# Sheet2.net
KiCad netlist of a schematic drawn in Altium Designer
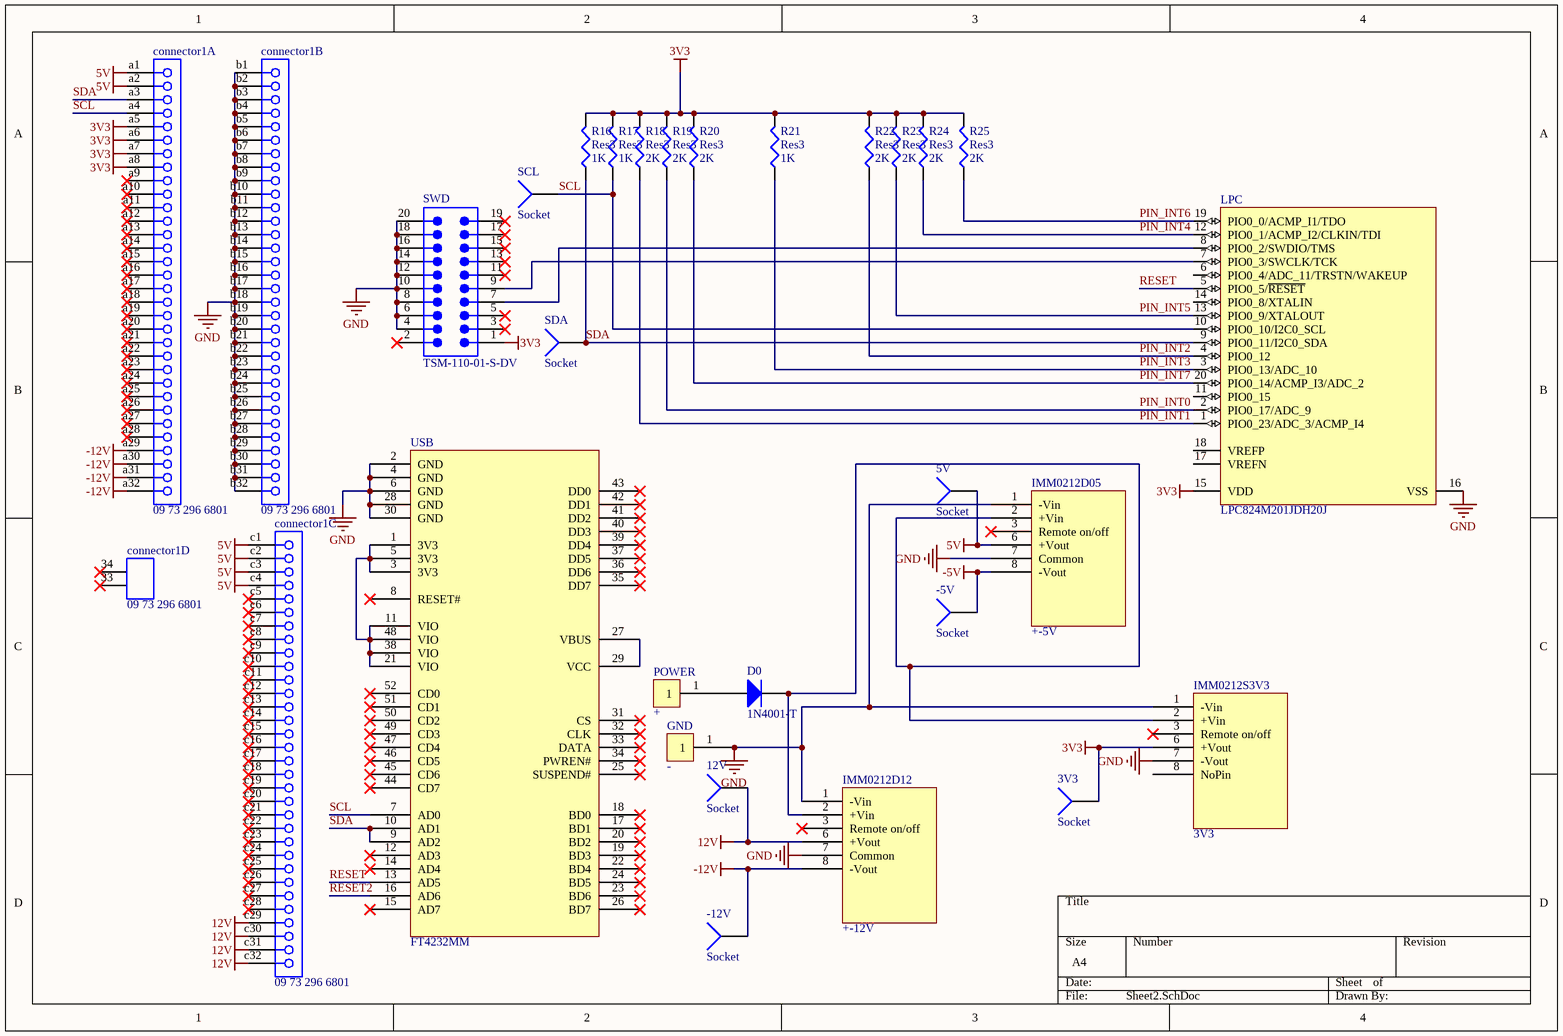
[diagram p0: Sheet2.SchDoc]

(export (version "E")
  (design (tool "Eeschema 10.0.6"))
  (components
    (comp (ref "-5V")
      (value "Socket")
      (footprint "CON1")
      (fields (field (name "PUBLISHER") "Altium Limited"))
      (libsource (lib "Miscellaneous Connectors") (part "Socket"))
    )
    (comp (ref "-12V")
      (value "Socket")
      (footprint "CON1")
      (fields (field (name "PUBLISHER") "Altium Limited"))
      (libsource (lib "Miscellaneous Connectors") (part "Socket"))
    )
    (comp (ref "3V3")
      (value "Socket")
      (footprint "CON1")
      (fields (field (name "PUBLISHER") "Altium Limited"))
      (libsource (lib "Miscellaneous Connectors") (part "Socket"))
    )
    (comp (ref "5V")
      (value "Socket")
      (footprint "CON1")
      (fields (field (name "PUBLISHER") "Altium Limited"))
      (libsource (lib "Miscellaneous Connectors") (part "Socket"))
    )
    (comp (ref "12V")
      (value "Socket")
      (footprint "CON1")
      (fields (field (name "PUBLISHER") "Altium Limited"))
      (libsource (lib "Miscellaneous Connectors") (part "Socket"))
    )
    (comp (ref "connector1")
      (value "09 73 296 6801")
      (footprint "DAC testerPCB:0973296X801")
      (fields (field (name "PUBLISHER") "Altium Limited"))
      (libsource (lib "HARTING DIN 41612 Type R") (part "09 73 296 6801"))
    )
    (comp (ref "D0")
      (value "1N4001-T")
      (footprint "DIOD-DO-41-P-2_V")
      (description "1.0 A Rectifier, 15 pF, 50 V, -65 to 150 degC, 2-Pin DO-41 Plastic, RoHS, Tape and Reel")
      (fields (field (name "MANUFACTURER") "Diodes Inc"))
      (libsource (lib "Altium Content Vault") (part "CMP-0639-00006-2"))
    )
    (comp (ref "GND") (value "-") (footprint "RA") (libsource (lib "schlib") (part "Power")))
    (comp (ref "IMM0212D05")
      (value "+-5V")
      (footprint "my_pcb:SIP8")
      (libsource (lib "schlib") (part "IMM0212D05"))
    )
    (comp (ref "IMM0212D12")
      (value "+-12V")
      (footprint "SIP8")
      (libsource (lib "schlib") (part "IMM0212D05"))
    )
    (comp (ref "IMM0212S3V3")
      (value "3V3")
      (footprint "my_pcb:SIP8")
      (libsource (lib "schlib") (part "Component_1"))
    )
    (comp (ref "LPC")
      (value "LPC824M201JDH20J")
      (footprint "NXP-SOT360-1_N")
      (fields
        (field (name "MANUFACTURER") "NXP Semiconductors")
        (field (name "PARTNUMBER") "LPC824M201JDH20")
      )
      (libsource (lib "Altium Content Vault") (part "CMP-0173-00095-1"))
    )
    (comp (ref "POWER") (value "+") (footprint "RA") (libsource (lib "schlib") (part "Power")))
    (comp (ref "R16")
      (value "Res3")
      (footprint "J1-0603")
      (description "Resistor")
      (fields (field (name "ALTIUM_VALUE") "1K") (field (name "PUBLISHER") "Altium Limited"))
      (libsource (lib "Miscellaneous Devices") (part "Res3"))
    )
    (comp (ref "R17")
      (value "Res3")
      (footprint "J1-0603")
      (description "Resistor")
      (fields (field (name "ALTIUM_VALUE") "1K") (field (name "PUBLISHER") "Altium Limited"))
      (libsource (lib "Miscellaneous Devices") (part "Res3"))
    )
    (comp (ref "R18")
      (value "Res3")
      (footprint "J1-0603")
      (description "Resistor")
      (fields (field (name "ALTIUM_VALUE") "2K") (field (name "PUBLISHER") "Altium Limited"))
      (libsource (lib "Miscellaneous Devices") (part "Res3"))
    )
    (comp (ref "R19")
      (value "Res3")
      (footprint "J1-0603")
      (description "Resistor")
      (fields (field (name "ALTIUM_VALUE") "2K") (field (name "PUBLISHER") "Altium Limited"))
      (libsource (lib "Miscellaneous Devices") (part "Res3"))
    )
    (comp (ref "R20")
      (value "Res3")
      (footprint "J1-0603")
      (description "Resistor")
      (fields (field (name "ALTIUM_VALUE") "2K") (field (name "PUBLISHER") "Altium Limited"))
      (libsource (lib "Miscellaneous Devices") (part "Res3"))
    )
    (comp (ref "R21")
      (value "Res3")
      (footprint "J1-0603")
      (description "Resistor")
      (fields (field (name "ALTIUM_VALUE") "1K") (field (name "PUBLISHER") "Altium Limited"))
      (libsource (lib "Miscellaneous Devices") (part "Res3"))
    )
    (comp (ref "R22")
      (value "Res3")
      (footprint "J1-0603")
      (description "Resistor")
      (fields (field (name "ALTIUM_VALUE") "2K") (field (name "PUBLISHER") "Altium Limited"))
      (libsource (lib "Miscellaneous Devices") (part "Res3"))
    )
    (comp (ref "R23")
      (value "Res3")
      (footprint "J1-0603")
      (description "Resistor")
      (fields (field (name "ALTIUM_VALUE") "2K") (field (name "PUBLISHER") "Altium Limited"))
      (libsource (lib "Miscellaneous Devices") (part "Res3"))
    )
    (comp (ref "R24")
      (value "Res3")
      (footprint "J1-0603")
      (description "Resistor")
      (fields (field (name "ALTIUM_VALUE") "2K") (field (name "PUBLISHER") "Altium Limited"))
      (libsource (lib "Miscellaneous Devices") (part "Res3"))
    )
    (comp (ref "R25")
      (value "Res3")
      (footprint "J1-0603")
      (description "Resistor")
      (fields (field (name "ALTIUM_VALUE") "2K") (field (name "PUBLISHER") "Altium Limited"))
      (libsource (lib "Miscellaneous Devices") (part "Res3"))
    )
    (comp (ref "SCL")
      (value "Socket")
      (footprint "CON1")
      (fields (field (name "PUBLISHER") "Altium Limited"))
      (libsource (lib "Miscellaneous Connectors") (part "Socket"))
    )
    (comp (ref "SDA")
      (value "Socket")
      (footprint "CON1")
      (fields (field (name "PUBLISHER") "Altium Limited"))
      (libsource (lib "Miscellaneous Connectors") (part "Socket"))
    )
    (comp (ref "SWD")
      (value "TSM-110-01-S-DV")
      (footprint "SMTC-TSM-110-01-X-DV")
      (fields (field (name "MANUFACTURER") "Samtec"))
      (libsource (lib "Altium Content Vault") (part "CMP-1024-00283-1"))
    )
    (comp (ref "USB")
      (value "FT4232MM")
      (footprint "ICfootprint3:FT4232MM")
      (description "FDTI mini module")
      (libsource (lib "nxp_device") (part "FT4232MM"))
    )
  )
  (nets
    (net (code "1") (name "-5V") (class "Default")
      (node (ref "-5V") (pin "1") (pinfunction "1_1") (pintype "passive"))
      (node (ref "IMM0212D05") (pin "8") (pinfunction "-Vout_8") (pintype "passive"))
    )
    (net (code "2") (name "-12V") (class "Default")
      (node (ref "-12V") (pin "1") (pinfunction "1_1") (pintype "passive"))
      (node (ref "IMM0212D12") (pin "8") (pinfunction "-Vout_8") (pintype "passive"))
      (node (ref "connector1") (pin "a29") (pinfunction "a29_a29") (pintype "passive"))
      (node (ref "connector1") (pin "a30") (pinfunction "a30_a30") (pintype "passive"))
      (node (ref "connector1") (pin "a31") (pinfunction "a31_a31") (pintype "passive"))
      (node (ref "connector1") (pin "a32") (pinfunction "a32_a32") (pintype "passive"))
    )
    (net (code "3") (name "/PIN_INT0") (class "Default")
      (node (ref "LPC") (pin "2") (pinfunction "PIO0_17/ADC_9_2") (pintype "bidirectional"))
      (node (ref "R19") (pin "1") (pinfunction "1_1") (pintype "passive"))
    )
    (net (code "4") (name "/PIN_INT1") (class "Default")
      (node (ref "LPC") (pin "1") (pinfunction "PIO0_23/ADC_3/ACMP_I4_1") (pintype "bidirectional"))
      (node (ref "R18") (pin "1") (pinfunction "1_1") (pintype "passive"))
    )
    (net (code "5") (name "/PIN_INT2") (class "Default")
      (node (ref "LPC") (pin "4") (pinfunction "PIO0_12_4") (pintype "bidirectional"))
      (node (ref "R22") (pin "1") (pinfunction "1_1") (pintype "passive"))
    )
    (net (code "6") (name "/PIN_INT3") (class "Default")
      (node (ref "LPC") (pin "3") (pinfunction "PIO0_13/ADC_10_3") (pintype "bidirectional"))
      (node (ref "R21") (pin "1") (pinfunction "1_1") (pintype "passive"))
    )
    (net (code "7") (name "/PIN_INT4") (class "Default")
      (node (ref "LPC") (pin "12") (pinfunction "PIO0_1/ACMP_I2/CLKIN/TDI_12") (pintype "bidirectional"))
      (node (ref "R24") (pin "1") (pinfunction "1_1") (pintype "passive"))
    )
    (net (code "8") (name "/PIN_INT5") (class "Default")
      (node (ref "LPC") (pin "13") (pinfunction "PIO0_9/XTALOUT_13") (pintype "bidirectional"))
      (node (ref "R23") (pin "1") (pinfunction "1_1") (pintype "passive"))
    )
    (net (code "9") (name "/PIN_INT6") (class "Default")
      (node (ref "LPC") (pin "19") (pinfunction "PIO0_0/ACMP_I1/TDO_19") (pintype "bidirectional"))
      (node (ref "R25") (pin "1") (pinfunction "1_1") (pintype "passive"))
    )
    (net (code "10") (name "/PIN_INT7") (class "Default")
      (node (ref "LPC") (pin "20") (pinfunction "PIO0_14/ACMP_I3/ADC_2_20") (pintype "bidirectional"))
      (node (ref "R20") (pin "1") (pinfunction "1_1") (pintype "passive"))
    )
    (net (code "11") (name "/RESET") (class "Default")
      (node (ref "LPC") (pin "5") (pinfunction "PIO0_5/~{RESET}_5") (pintype "bidirectional"))
      (node (ref "USB") (pin "13") (pinfunction "AD5_13") (pintype "passive"))
    )
    (net (code "12") (name "/RESET2") (class "Default")
      (node (ref "USB") (pin "16") (pinfunction "AD6_16") (pintype "passive"))
    )
    (net (code "13") (name "/SCL") (class "Default")
      (node (ref "LPC") (pin "10") (pinfunction "PIO0_10/I2C0_SCL_10") (pintype "bidirectional"))
      (node (ref "R17") (pin "1") (pinfunction "1_1") (pintype "passive"))
      (node (ref "SCL") (pin "1") (pinfunction "1_1") (pintype "passive"))
      (node (ref "USB") (pin "7") (pinfunction "AD0_7") (pintype "passive"))
      (node (ref "connector1") (pin "a4") (pinfunction "a4_a4") (pintype "passive"))
    )
    (net (code "14") (name "/SDA") (class "Default")
      (node (ref "LPC") (pin "9") (pinfunction "PIO0_11/I2C0_SDA_9") (pintype "bidirectional"))
      (node (ref "R16") (pin "1") (pinfunction "1_1") (pintype "passive"))
      (node (ref "SDA") (pin "1") (pinfunction "1_1") (pintype "passive"))
      (node (ref "USB") (pin "10") (pinfunction "AD1_10") (pintype "passive"))
      (node (ref "USB") (pin "9") (pinfunction "AD2_9") (pintype "passive"))
      (node (ref "connector1") (pin "a3") (pinfunction "a3_a3") (pintype "passive"))
    )
    (net (code "15") (name "3V3") (class "Default")
      (node (ref "3V3") (pin "1") (pinfunction "1_1") (pintype "passive"))
      (node (ref "IMM0212S3V3") (pin "6") (pinfunction "+Vout_6") (pintype "passive"))
      (node (ref "LPC") (pin "15") (pinfunction "VDD_15") (pintype "power_in"))
      (node (ref "R16") (pin "2") (pinfunction "2_2") (pintype "passive"))
      (node (ref "R17") (pin "2") (pinfunction "2_2") (pintype "passive"))
      (node (ref "R18") (pin "2") (pinfunction "2_2") (pintype "passive"))
      (node (ref "R19") (pin "2") (pinfunction "2_2") (pintype "passive"))
      (node (ref "R20") (pin "2") (pinfunction "2_2") (pintype "passive"))
      (node (ref "R21") (pin "2") (pinfunction "2_2") (pintype "passive"))
      (node (ref "R22") (pin "2") (pinfunction "2_2") (pintype "passive"))
      (node (ref "R23") (pin "2") (pinfunction "2_2") (pintype "passive"))
      (node (ref "R24") (pin "2") (pinfunction "2_2") (pintype "passive"))
      (node (ref "R25") (pin "2") (pinfunction "2_2") (pintype "passive"))
      (node (ref "SWD") (pin "1") (pinfunction "1_1") (pintype "passive"))
      (node (ref "connector1") (pin "a5") (pinfunction "a5_a5") (pintype "passive"))
      (node (ref "connector1") (pin "a6") (pinfunction "a6_a6") (pintype "passive"))
      (node (ref "connector1") (pin "a7") (pinfunction "a7_a7") (pintype "passive"))
      (node (ref "connector1") (pin "a8") (pinfunction "a8_a8") (pintype "passive"))
    )
    (net (code "16") (name "5V") (class "Default")
      (node (ref "5V") (pin "1") (pinfunction "1_1") (pintype "passive"))
      (node (ref "IMM0212D05") (pin "6") (pinfunction "+Vout_6") (pintype "passive"))
      (node (ref "connector1") (pin "a1") (pinfunction "a1_a1") (pintype "passive"))
      (node (ref "connector1") (pin "a2") (pinfunction "a2_a2") (pintype "passive"))
      (node (ref "connector1") (pin "c1") (pinfunction "c1_c1") (pintype "passive"))
      (node (ref "connector1") (pin "c2") (pinfunction "c2_c2") (pintype "passive"))
      (node (ref "connector1") (pin "c3") (pinfunction "c3_c3") (pintype "passive"))
      (node (ref "connector1") (pin "c4") (pinfunction "c4_c4") (pintype "passive"))
    )
    (net (code "17") (name "12V") (class "Default")
      (node (ref "12V") (pin "1") (pinfunction "1_1") (pintype "passive"))
      (node (ref "IMM0212D12") (pin "6") (pinfunction "+Vout_6") (pintype "passive"))
      (node (ref "connector1") (pin "c29") (pinfunction "c29_c29") (pintype "passive"))
      (node (ref "connector1") (pin "c30") (pinfunction "c30_c30") (pintype "passive"))
      (node (ref "connector1") (pin "c31") (pinfunction "c31_c31") (pintype "passive"))
      (node (ref "connector1") (pin "c32") (pinfunction "c32_c32") (pintype "passive"))
    )
    (net (code "18") (name "GND") (class "Default")
      (node (ref "GND") (pin "1") (pinfunction "1_1") (pintype "passive"))
      (node (ref "IMM0212D05") (pin "1") (pinfunction "-Vin_1") (pintype "passive"))
      (node (ref "IMM0212D05") (pin "7") (pinfunction "Common_7") (pintype "passive"))
      (node (ref "IMM0212D12") (pin "1") (pinfunction "-Vin_1") (pintype "passive"))
      (node (ref "IMM0212D12") (pin "7") (pinfunction "Common_7") (pintype "passive"))
      (node (ref "IMM0212S3V3") (pin "1") (pinfunction "-Vin_1") (pintype "passive"))
      (node (ref "IMM0212S3V3") (pin "7") (pinfunction "-Vout_7") (pintype "passive"))
      (node (ref "LPC") (pin "16") (pinfunction "VSS_16") (pintype "power_in"))
      (node (ref "SWD") (pin "10") (pinfunction "10_10") (pintype "passive"))
      (node (ref "SWD") (pin "12") (pinfunction "12_12") (pintype "passive"))
      (node (ref "SWD") (pin "14") (pinfunction "14_14") (pintype "passive"))
      (node (ref "SWD") (pin "16") (pinfunction "16_16") (pintype "passive"))
      (node (ref "SWD") (pin "18") (pinfunction "18_18") (pintype "passive"))
      (node (ref "SWD") (pin "20") (pinfunction "20_20") (pintype "passive"))
      (node (ref "SWD") (pin "4") (pinfunction "4_4") (pintype "passive"))
      (node (ref "SWD") (pin "6") (pinfunction "6_6") (pintype "passive"))
      (node (ref "SWD") (pin "8") (pinfunction "8_8") (pintype "passive"))
      (node (ref "USB") (pin "2") (pinfunction "GND_2") (pintype "passive"))
      (node (ref "USB") (pin "28") (pinfunction "GND_28") (pintype "passive"))
      (node (ref "USB") (pin "30") (pinfunction "GND_30") (pintype "passive"))
      (node (ref "USB") (pin "4") (pinfunction "GND_4") (pintype "passive"))
      (node (ref "USB") (pin "6") (pinfunction "GND_6") (pintype "passive"))
      (node (ref "connector1") (pin "b1") (pinfunction "b1_b1") (pintype "passive"))
      (node (ref "connector1") (pin "b10") (pinfunction "b10_b10") (pintype "passive"))
      (node (ref "connector1") (pin "b11") (pinfunction "b11_b11") (pintype "passive"))
      (node (ref "connector1") (pin "b12") (pinfunction "b12_b12") (pintype "passive"))
      (node (ref "connector1") (pin "b13") (pinfunction "b13_b13") (pintype "passive"))
      (node (ref "connector1") (pin "b14") (pinfunction "b14_b14") (pintype "passive"))
      (node (ref "connector1") (pin "b15") (pinfunction "b15_b15") (pintype "passive"))
      (node (ref "connector1") (pin "b16") (pinfunction "b16_b16") (pintype "passive"))
      (node (ref "connector1") (pin "b17") (pinfunction "b17_b17") (pintype "passive"))
      (node (ref "connector1") (pin "b18") (pinfunction "b18_b18") (pintype "passive"))
      (node (ref "connector1") (pin "b19") (pinfunction "b19_b19") (pintype "passive"))
      (node (ref "connector1") (pin "b2") (pinfunction "b2_b2") (pintype "passive"))
      (node (ref "connector1") (pin "b20") (pinfunction "b20_b20") (pintype "passive"))
      (node (ref "connector1") (pin "b21") (pinfunction "b21_b21") (pintype "passive"))
      (node (ref "connector1") (pin "b22") (pinfunction "b22_b22") (pintype "passive"))
      (node (ref "connector1") (pin "b23") (pinfunction "b23_b23") (pintype "passive"))
      (node (ref "connector1") (pin "b24") (pinfunction "b24_b24") (pintype "passive"))
      (node (ref "connector1") (pin "b25") (pinfunction "b25_b25") (pintype "passive"))
      (node (ref "connector1") (pin "b26") (pinfunction "b26_b26") (pintype "passive"))
      (node (ref "connector1") (pin "b27") (pinfunction "b27_b27") (pintype "passive"))
      (node (ref "connector1") (pin "b28") (pinfunction "b28_b28") (pintype "passive"))
      (node (ref "connector1") (pin "b29") (pinfunction "b29_b29") (pintype "passive"))
      (node (ref "connector1") (pin "b3") (pinfunction "b3_b3") (pintype "passive"))
      (node (ref "connector1") (pin "b30") (pinfunction "b30_b30") (pintype "passive"))
      (node (ref "connector1") (pin "b31") (pinfunction "b31_b31") (pintype "passive"))
      (node (ref "connector1") (pin "b32") (pinfunction "b32_b32") (pintype "passive"))
      (node (ref "connector1") (pin "b4") (pinfunction "b4_b4") (pintype "passive"))
      (node (ref "connector1") (pin "b5") (pinfunction "b5_b5") (pintype "passive"))
      (node (ref "connector1") (pin "b6") (pinfunction "b6_b6") (pintype "passive"))
      (node (ref "connector1") (pin "b7") (pinfunction "b7_b7") (pintype "passive"))
      (node (ref "connector1") (pin "b8") (pinfunction "b8_b8") (pintype "passive"))
      (node (ref "connector1") (pin "b9") (pinfunction "b9_b9") (pintype "passive"))
    )
    (net (code "19") (name "Net-(D0-A)") (class "Default")
      (node (ref "D0") (pin "1") (pinfunction "A_1") (pintype "passive"))
      (node (ref "POWER") (pin "1") (pinfunction "1_1") (pintype "passive"))
    )
    (net (code "20") (name "Net-(D0-K)") (class "Default")
      (node (ref "D0") (pin "2") (pinfunction "K_2") (pintype "passive"))
      (node (ref "IMM0212D05") (pin "2") (pinfunction "+Vin_2") (pintype "passive"))
      (node (ref "IMM0212D12") (pin "2") (pinfunction "+Vin_2") (pintype "passive"))
      (node (ref "IMM0212S3V3") (pin "2") (pinfunction "+Vin_2") (pintype "passive"))
    )
    (net (code "21") (name "Net-(LPC-PIO0_2{slash}SWDIO{slash}TMS)") (class "Default")
      (node (ref "LPC") (pin "8") (pinfunction "PIO0_2/SWDIO/TMS_8") (pintype "bidirectional"))
      (node (ref "SWD") (pin "7") (pinfunction "7_7") (pintype "passive"))
    )
    (net (code "22") (name "Net-(LPC-PIO0_3{slash}SWCLK{slash}TCK)") (class "Default")
      (node (ref "LPC") (pin "7") (pinfunction "PIO0_3/SWCLK/TCK_7") (pintype "bidirectional"))
      (node (ref "SWD") (pin "9") (pinfunction "9_9") (pintype "passive"))
    )
    (net (code "23") (name "Net-(USB-3V3-Pad1)") (class "Default")
      (node (ref "USB") (pin "1") (pinfunction "3V3_1") (pintype "passive"))
      (node (ref "USB") (pin "11") (pinfunction "VIO_11") (pintype "passive"))
      (node (ref "USB") (pin "21") (pinfunction "VIO_21") (pintype "passive"))
      (node (ref "USB") (pin "3") (pinfunction "3V3_3") (pintype "passive"))
      (node (ref "USB") (pin "38") (pinfunction "VIO_38") (pintype "passive"))
      (node (ref "USB") (pin "48") (pinfunction "VIO_48") (pintype "passive"))
      (node (ref "USB") (pin "5") (pinfunction "3V3_5") (pintype "passive"))
    )
    (net (code "24") (name "Net-(USB-VBUS)") (class "Default")
      (node (ref "USB") (pin "27") (pinfunction "VBUS_27") (pintype "passive"))
      (node (ref "USB") (pin "29") (pinfunction "VCC_29") (pintype "passive"))
    )
    (net (code "25") (name "unconnected-(IMM0212D05-Remote_on{slash}off-Pad3)") (class "Default")
      (node (ref "IMM0212D05") (pin "3") (pinfunction "Remote_on/off_3") (pintype "passive+no_connect"))
    )
    (net (code "26") (name "unconnected-(IMM0212D12-Remote_on{slash}off-Pad3)") (class "Default")
      (node (ref "IMM0212D12") (pin "3") (pinfunction "Remote_on/off_3") (pintype "passive+no_connect"))
    )
    (net (code "27") (name "unconnected-(IMM0212S3V3-NoPin-Pad8)") (class "Default")
      (node (ref "IMM0212S3V3") (pin "8") (pinfunction "NoPin_8") (pintype "passive"))
    )
    (net (code "28") (name "unconnected-(IMM0212S3V3-Remote_on{slash}off-Pad3)") (class "Default")
      (node (ref "IMM0212S3V3") (pin "3") (pinfunction "Remote_on/off_3") (pintype "passive+no_connect"))
    )
    (net (code "29") (name "unconnected-(LPC-PIO0_4{slash}ADC_11{slash}TRSTN{slash}WAKEUP-Pad6)") (class "Default")
      (node (ref "LPC") (pin "6") (pinfunction "PIO0_4/ADC_11/TRSTN/WAKEUP_6") (pintype "bidirectional"))
    )
    (net (code "30") (name "unconnected-(LPC-PIO0_8{slash}XTALIN-Pad14)") (class "Default")
      (node (ref "LPC") (pin "14") (pinfunction "PIO0_8/XTALIN_14") (pintype "bidirectional"))
    )
    (net (code "31") (name "unconnected-(LPC-PIO0_15-Pad11)") (class "Default")
      (node (ref "LPC") (pin "11") (pinfunction "PIO0_15_11") (pintype "bidirectional"))
    )
    (net (code "32") (name "unconnected-(LPC-VREFN-Pad17)") (class "Default")
      (node (ref "LPC") (pin "17") (pinfunction "VREFN_17") (pintype "power_in"))
    )
    (net (code "33") (name "unconnected-(LPC-VREFP-Pad18)") (class "Default")
      (node (ref "LPC") (pin "18") (pinfunction "VREFP_18") (pintype "power_in"))
    )
    (net (code "34") (name "unconnected-(SWD-Pad2)") (class "Default")
      (node (ref "SWD") (pin "2") (pinfunction "2_2") (pintype "passive+no_connect"))
    )
    (net (code "35") (name "unconnected-(SWD-Pad3)") (class "Default")
      (node (ref "SWD") (pin "3") (pinfunction "3_3") (pintype "passive+no_connect"))
    )
    (net (code "36") (name "unconnected-(SWD-Pad5)") (class "Default")
      (node (ref "SWD") (pin "5") (pinfunction "5_5") (pintype "passive+no_connect"))
    )
    (net (code "37") (name "unconnected-(SWD-Pad11)") (class "Default")
      (node (ref "SWD") (pin "11") (pinfunction "11_11") (pintype "passive+no_connect"))
    )
    (net (code "38") (name "unconnected-(SWD-Pad13)") (class "Default")
      (node (ref "SWD") (pin "13") (pinfunction "13_13") (pintype "passive+no_connect"))
    )
    (net (code "39") (name "unconnected-(SWD-Pad15)") (class "Default")
      (node (ref "SWD") (pin "15") (pinfunction "15_15") (pintype "passive+no_connect"))
    )
    (net (code "40") (name "unconnected-(SWD-Pad17)") (class "Default")
      (node (ref "SWD") (pin "17") (pinfunction "17_17") (pintype "passive+no_connect"))
    )
    (net (code "41") (name "unconnected-(SWD-Pad19)") (class "Default")
      (node (ref "SWD") (pin "19") (pinfunction "19_19") (pintype "passive+no_connect"))
    )
    (net (code "42") (name "unconnected-(USB-AD3-Pad12)") (class "Default")
      (node (ref "USB") (pin "12") (pinfunction "AD3_12") (pintype "passive+no_connect"))
    )
    (net (code "43") (name "unconnected-(USB-AD4-Pad14)") (class "Default")
      (node (ref "USB") (pin "14") (pinfunction "AD4_14") (pintype "passive+no_connect"))
    )
    (net (code "44") (name "unconnected-(USB-AD7-Pad15)") (class "Default")
      (node (ref "USB") (pin "15") (pinfunction "AD7_15") (pintype "passive+no_connect"))
    )
    (net (code "45") (name "unconnected-(USB-BD0-Pad18)") (class "Default")
      (node (ref "USB") (pin "18") (pinfunction "BD0_18") (pintype "passive+no_connect"))
    )
    (net (code "46") (name "unconnected-(USB-BD1-Pad17)") (class "Default")
      (node (ref "USB") (pin "17") (pinfunction "BD1_17") (pintype "passive+no_connect"))
    )
    (net (code "47") (name "unconnected-(USB-BD2-Pad20)") (class "Default")
      (node (ref "USB") (pin "20") (pinfunction "BD2_20") (pintype "passive+no_connect"))
    )
    (net (code "48") (name "unconnected-(USB-BD3-Pad19)") (class "Default")
      (node (ref "USB") (pin "19") (pinfunction "BD3_19") (pintype "passive+no_connect"))
    )
    (net (code "49") (name "unconnected-(USB-BD4-Pad22)") (class "Default")
      (node (ref "USB") (pin "22") (pinfunction "BD4_22") (pintype "passive+no_connect"))
    )
    (net (code "50") (name "unconnected-(USB-BD5-Pad24)") (class "Default")
      (node (ref "USB") (pin "24") (pinfunction "BD5_24") (pintype "passive+no_connect"))
    )
    (net (code "51") (name "unconnected-(USB-BD6-Pad23)") (class "Default")
      (node (ref "USB") (pin "23") (pinfunction "BD6_23") (pintype "passive+no_connect"))
    )
    (net (code "52") (name "unconnected-(USB-BD7-Pad26)") (class "Default")
      (node (ref "USB") (pin "26") (pinfunction "BD7_26") (pintype "passive+no_connect"))
    )
    (net (code "53") (name "unconnected-(USB-CD0-Pad52)") (class "Default")
      (node (ref "USB") (pin "52") (pinfunction "CD0_52") (pintype "passive+no_connect"))
    )
    (net (code "54") (name "unconnected-(USB-CD1-Pad51)") (class "Default")
      (node (ref "USB") (pin "51") (pinfunction "CD1_51") (pintype "passive+no_connect"))
    )
    (net (code "55") (name "unconnected-(USB-CD2-Pad50)") (class "Default")
      (node (ref "USB") (pin "50") (pinfunction "CD2_50") (pintype "passive+no_connect"))
    )
    (net (code "56") (name "unconnected-(USB-CD3-Pad49)") (class "Default")
      (node (ref "USB") (pin "49") (pinfunction "CD3_49") (pintype "passive+no_connect"))
    )
    (net (code "57") (name "unconnected-(USB-CD4-Pad47)") (class "Default")
      (node (ref "USB") (pin "47") (pinfunction "CD4_47") (pintype "passive+no_connect"))
    )
    (net (code "58") (name "unconnected-(USB-CD5-Pad46)") (class "Default")
      (node (ref "USB") (pin "46") (pinfunction "CD5_46") (pintype "passive+no_connect"))
    )
    (net (code "59") (name "unconnected-(USB-CD6-Pad45)") (class "Default")
      (node (ref "USB") (pin "45") (pinfunction "CD6_45") (pintype "passive+no_connect"))
    )
    (net (code "60") (name "unconnected-(USB-CD7-Pad44)") (class "Default")
      (node (ref "USB") (pin "44") (pinfunction "CD7_44") (pintype "passive+no_connect"))
    )
    (net (code "61") (name "unconnected-(USB-CLK-Pad32)") (class "Default")
      (node (ref "USB") (pin "32") (pinfunction "CLK_32") (pintype "passive+no_connect"))
    )
    (net (code "62") (name "unconnected-(USB-CS-Pad31)") (class "Default")
      (node (ref "USB") (pin "31") (pinfunction "CS_31") (pintype "passive+no_connect"))
    )
    (net (code "63") (name "unconnected-(USB-DATA-Pad33)") (class "Default")
      (node (ref "USB") (pin "33") (pinfunction "DATA_33") (pintype "passive+no_connect"))
    )
    (net (code "64") (name "unconnected-(USB-DD0-Pad43)") (class "Default")
      (node (ref "USB") (pin "43") (pinfunction "DD0_43") (pintype "passive+no_connect"))
    )
    (net (code "65") (name "unconnected-(USB-DD1-Pad42)") (class "Default")
      (node (ref "USB") (pin "42") (pinfunction "DD1_42") (pintype "passive+no_connect"))
    )
    (net (code "66") (name "unconnected-(USB-DD2-Pad41)") (class "Default")
      (node (ref "USB") (pin "41") (pinfunction "DD2_41") (pintype "passive+no_connect"))
    )
    (net (code "67") (name "unconnected-(USB-DD3-Pad40)") (class "Default")
      (node (ref "USB") (pin "40") (pinfunction "DD3_40") (pintype "passive+no_connect"))
    )
    (net (code "68") (name "unconnected-(USB-DD4-Pad39)") (class "Default")
      (node (ref "USB") (pin "39") (pinfunction "DD4_39") (pintype "passive+no_connect"))
    )
    (net (code "69") (name "unconnected-(USB-DD5-Pad37)") (class "Default")
      (node (ref "USB") (pin "37") (pinfunction "DD5_37") (pintype "passive+no_connect"))
    )
    (net (code "70") (name "unconnected-(USB-DD6-Pad36)") (class "Default")
      (node (ref "USB") (pin "36") (pinfunction "DD6_36") (pintype "passive+no_connect"))
    )
    (net (code "71") (name "unconnected-(USB-DD7-Pad35)") (class "Default")
      (node (ref "USB") (pin "35") (pinfunction "DD7_35") (pintype "passive+no_connect"))
    )
    (net (code "72") (name "unconnected-(USB-PWREN#-Pad34)") (class "Default")
      (node (ref "USB") (pin "34") (pinfunction "PWREN#_34") (pintype "passive+no_connect"))
    )
    (net (code "73") (name "unconnected-(USB-RESET#-Pad8)") (class "Default")
      (node (ref "USB") (pin "8") (pinfunction "RESET#_8") (pintype "passive+no_connect"))
    )
    (net (code "74") (name "unconnected-(USB-SUSPEND#-Pad25)") (class "Default")
      (node (ref "USB") (pin "25") (pinfunction "SUSPEND#_25") (pintype "passive+no_connect"))
    )
    (net (code "75") (name "unconnected-(connector1-Pada9)") (class "Default")
      (node (ref "connector1") (pin "a9") (pinfunction "a9_a9") (pintype "passive+no_connect"))
    )
    (net (code "76") (name "unconnected-(connector1-Pada10)") (class "Default")
      (node (ref "connector1") (pin "a10") (pinfunction "a10_a10") (pintype "passive+no_connect"))
    )
    (net (code "77") (name "unconnected-(connector1-Pada11)") (class "Default")
      (node (ref "connector1") (pin "a11") (pinfunction "a11_a11") (pintype "passive+no_connect"))
    )
    (net (code "78") (name "unconnected-(connector1-Pada12)") (class "Default")
      (node (ref "connector1") (pin "a12") (pinfunction "a12_a12") (pintype "passive+no_connect"))
    )
    (net (code "79") (name "unconnected-(connector1-Pada13)") (class "Default")
      (node (ref "connector1") (pin "a13") (pinfunction "a13_a13") (pintype "passive+no_connect"))
    )
    (net (code "80") (name "unconnected-(connector1-Pada14)") (class "Default")
      (node (ref "connector1") (pin "a14") (pinfunction "a14_a14") (pintype "passive+no_connect"))
    )
    (net (code "81") (name "unconnected-(connector1-Pada15)") (class "Default")
      (node (ref "connector1") (pin "a15") (pinfunction "a15_a15") (pintype "passive+no_connect"))
    )
    (net (code "82") (name "unconnected-(connector1-Pada16)") (class "Default")
      (node (ref "connector1") (pin "a16") (pinfunction "a16_a16") (pintype "passive+no_connect"))
    )
    (net (code "83") (name "unconnected-(connector1-Pada17)") (class "Default")
      (node (ref "connector1") (pin "a17") (pinfunction "a17_a17") (pintype "passive+no_connect"))
    )
    (net (code "84") (name "unconnected-(connector1-Pada18)") (class "Default")
      (node (ref "connector1") (pin "a18") (pinfunction "a18_a18") (pintype "passive+no_connect"))
    )
    (net (code "85") (name "unconnected-(connector1-Pada19)") (class "Default")
      (node (ref "connector1") (pin "a19") (pinfunction "a19_a19") (pintype "passive+no_connect"))
    )
    (net (code "86") (name "unconnected-(connector1-Pada20)") (class "Default")
      (node (ref "connector1") (pin "a20") (pinfunction "a20_a20") (pintype "passive+no_connect"))
    )
    (net (code "87") (name "unconnected-(connector1-Pada21)") (class "Default")
      (node (ref "connector1") (pin "a21") (pinfunction "a21_a21") (pintype "passive+no_connect"))
    )
    (net (code "88") (name "unconnected-(connector1-Pada22)") (class "Default")
      (node (ref "connector1") (pin "a22") (pinfunction "a22_a22") (pintype "passive+no_connect"))
    )
    (net (code "89") (name "unconnected-(connector1-Pada23)") (class "Default")
      (node (ref "connector1") (pin "a23") (pinfunction "a23_a23") (pintype "passive+no_connect"))
    )
    (net (code "90") (name "unconnected-(connector1-Pada24)") (class "Default")
      (node (ref "connector1") (pin "a24") (pinfunction "a24_a24") (pintype "passive+no_connect"))
    )
    (net (code "91") (name "unconnected-(connector1-Pada25)") (class "Default")
      (node (ref "connector1") (pin "a25") (pinfunction "a25_a25") (pintype "passive+no_connect"))
    )
    (net (code "92") (name "unconnected-(connector1-Pada26)") (class "Default")
      (node (ref "connector1") (pin "a26") (pinfunction "a26_a26") (pintype "passive+no_connect"))
    )
    (net (code "93") (name "unconnected-(connector1-Pada27)") (class "Default")
      (node (ref "connector1") (pin "a27") (pinfunction "a27_a27") (pintype "passive+no_connect"))
    )
    (net (code "94") (name "unconnected-(connector1-Pada28)") (class "Default")
      (node (ref "connector1") (pin "a28") (pinfunction "a28_a28") (pintype "passive+no_connect"))
    )
    (net (code "95") (name "unconnected-(connector1-Padc5)") (class "Default")
      (node (ref "connector1") (pin "c5") (pinfunction "c5_c5") (pintype "passive+no_connect"))
    )
    (net (code "96") (name "unconnected-(connector1-Padc6)") (class "Default")
      (node (ref "connector1") (pin "c6") (pinfunction "c6_c6") (pintype "passive+no_connect"))
    )
    (net (code "97") (name "unconnected-(connector1-Padc7)") (class "Default")
      (node (ref "connector1") (pin "c7") (pinfunction "c7_c7") (pintype "passive+no_connect"))
    )
    (net (code "98") (name "unconnected-(connector1-Padc8)") (class "Default")
      (node (ref "connector1") (pin "c8") (pinfunction "c8_c8") (pintype "passive+no_connect"))
    )
    (net (code "99") (name "unconnected-(connector1-Padc9)") (class "Default")
      (node (ref "connector1") (pin "c9") (pinfunction "c9_c9") (pintype "passive+no_connect"))
    )
    (net (code "100") (name "unconnected-(connector1-Padc10)") (class "Default")
      (node (ref "connector1") (pin "c10") (pinfunction "c10_c10") (pintype "passive+no_connect"))
    )
    (net (code "101") (name "unconnected-(connector1-Padc11)") (class "Default")
      (node (ref "connector1") (pin "c11") (pinfunction "c11_c11") (pintype "passive+no_connect"))
    )
    (net (code "102") (name "unconnected-(connector1-Padc12)") (class "Default")
      (node (ref "connector1") (pin "c12") (pinfunction "c12_c12") (pintype "passive+no_connect"))
    )
    (net (code "103") (name "unconnected-(connector1-Padc13)") (class "Default")
      (node (ref "connector1") (pin "c13") (pinfunction "c13_c13") (pintype "passive+no_connect"))
    )
    (net (code "104") (name "unconnected-(connector1-Padc14)") (class "Default")
      (node (ref "connector1") (pin "c14") (pinfunction "c14_c14") (pintype "passive+no_connect"))
    )
    (net (code "105") (name "unconnected-(connector1-Padc15)") (class "Default")
      (node (ref "connector1") (pin "c15") (pinfunction "c15_c15") (pintype "passive+no_connect"))
    )
    (net (code "106") (name "unconnected-(connector1-Padc16)") (class "Default")
      (node (ref "connector1") (pin "c16") (pinfunction "c16_c16") (pintype "passive+no_connect"))
    )
    (net (code "107") (name "unconnected-(connector1-Padc17)") (class "Default")
      (node (ref "connector1") (pin "c17") (pinfunction "c17_c17") (pintype "passive+no_connect"))
    )
    (net (code "108") (name "unconnected-(connector1-Padc18)") (class "Default")
      (node (ref "connector1") (pin "c18") (pinfunction "c18_c18") (pintype "passive+no_connect"))
    )
    (net (code "109") (name "unconnected-(connector1-Padc19)") (class "Default")
      (node (ref "connector1") (pin "c19") (pinfunction "c19_c19") (pintype "passive+no_connect"))
    )
    (net (code "110") (name "unconnected-(connector1-Padc20)") (class "Default")
      (node (ref "connector1") (pin "c20") (pinfunction "c20_c20") (pintype "passive+no_connect"))
    )
    (net (code "111") (name "unconnected-(connector1-Padc21)") (class "Default")
      (node (ref "connector1") (pin "c21") (pinfunction "c21_c21") (pintype "passive+no_connect"))
    )
    (net (code "112") (name "unconnected-(connector1-Padc22)") (class "Default")
      (node (ref "connector1") (pin "c22") (pinfunction "c22_c22") (pintype "passive+no_connect"))
    )
    (net (code "113") (name "unconnected-(connector1-Padc23)") (class "Default")
      (node (ref "connector1") (pin "c23") (pinfunction "c23_c23") (pintype "passive+no_connect"))
    )
    (net (code "114") (name "unconnected-(connector1-Padc24)") (class "Default")
      (node (ref "connector1") (pin "c24") (pinfunction "c24_c24") (pintype "passive+no_connect"))
    )
    (net (code "115") (name "unconnected-(connector1-Padc25)") (class "Default")
      (node (ref "connector1") (pin "c25") (pinfunction "c25_c25") (pintype "passive+no_connect"))
    )
    (net (code "116") (name "unconnected-(connector1-Padc26)") (class "Default")
      (node (ref "connector1") (pin "c26") (pinfunction "c26_c26") (pintype "passive+no_connect"))
    )
    (net (code "117") (name "unconnected-(connector1-Padc27)") (class "Default")
      (node (ref "connector1") (pin "c27") (pinfunction "c27_c27") (pintype "passive+no_connect"))
    )
    (net (code "118") (name "unconnected-(connector1-Padc28)") (class "Default")
      (node (ref "connector1") (pin "c28") (pinfunction "c28_c28") (pintype "passive+no_connect"))
    )
    (net (code "119") (name "unconnected-(connector1D-MH1-Pad33)") (class "Default")
      (node (ref "connector1") (pin "33") (pinfunction "MH1_33") (pintype "passive+no_connect"))
    )
    (net (code "120") (name "unconnected-(connector1D-MH2-Pad34)") (class "Default")
      (node (ref "connector1") (pin "34") (pinfunction "MH2_34") (pintype "passive+no_connect"))
    )
  )
)
